# CH32M030G8R7_1V1.net
KiCad netlist of a schematic drawn in Altium Designer
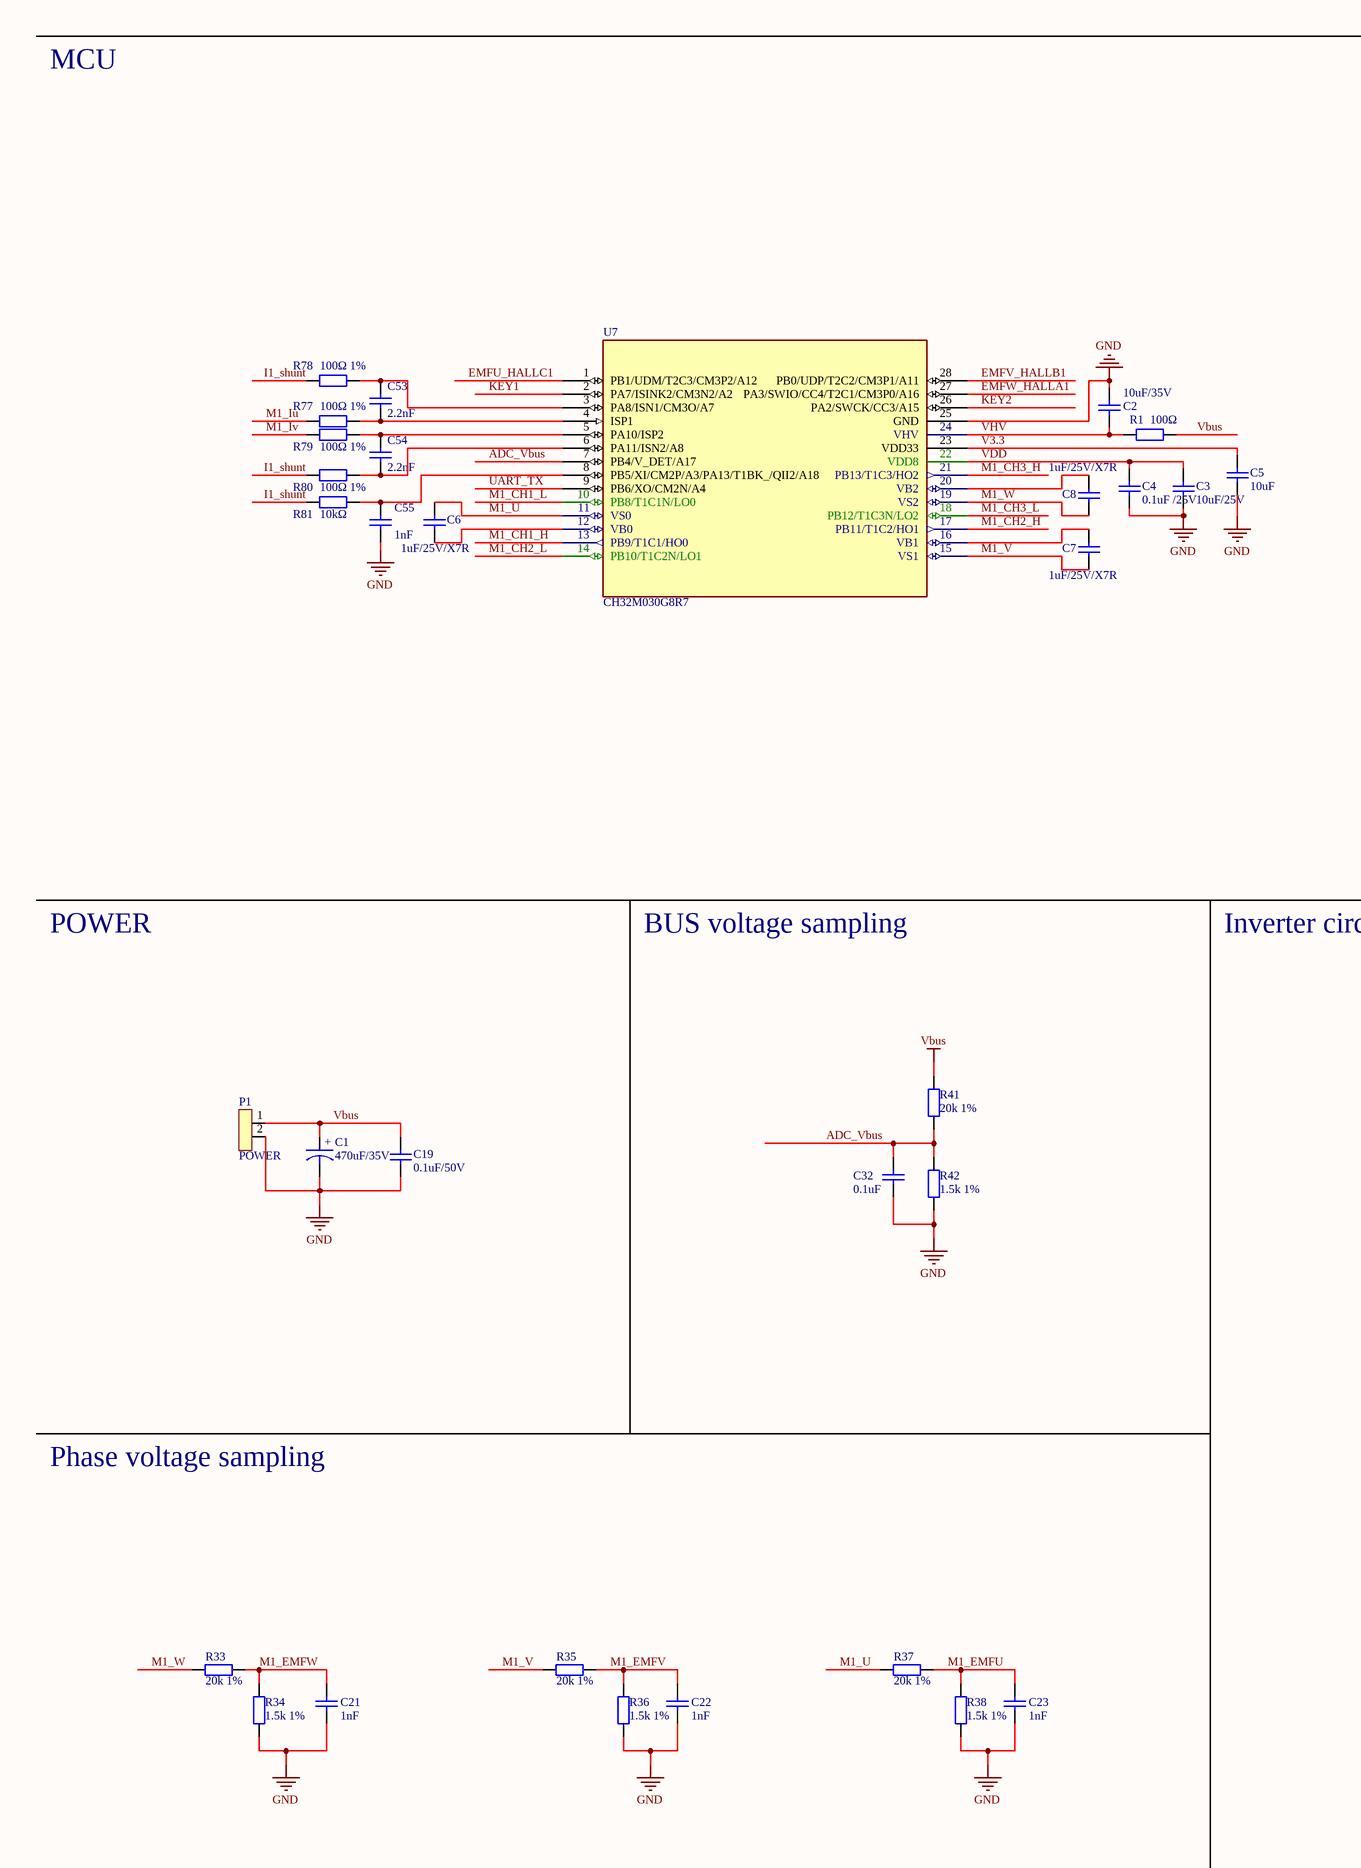
[diagram p0: CH32M030G8R7_1V1.SchDoc, left]
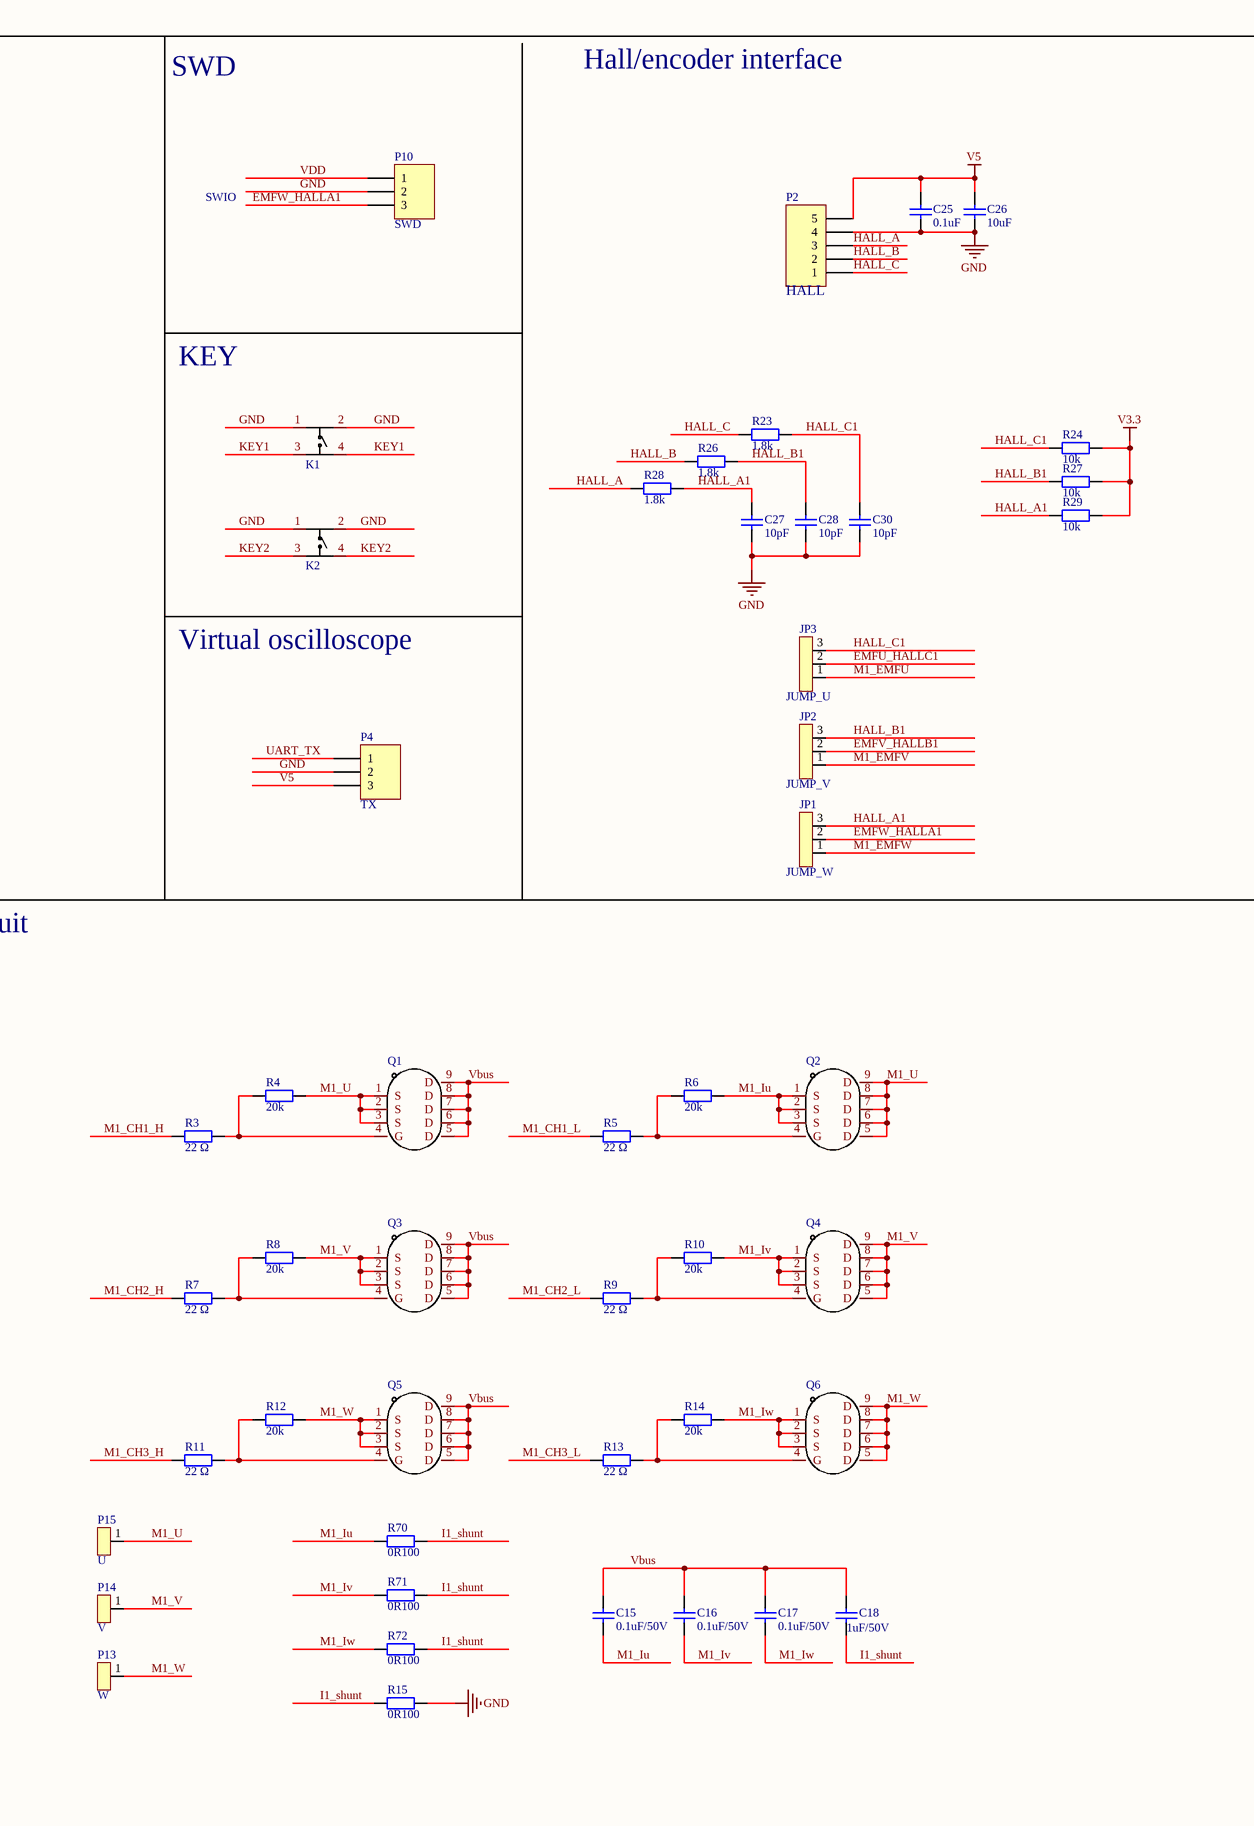
[diagram p1: CH32M030G8R7_1V1.SchDoc, right]

(export (version "E")
  (design (tool "Eeschema 10.0.6"))
  (components
    (comp (ref "C1")
      (value "470uF/35V")
      (footprint "M_C_RB_D10F5")
      (description "Capacitor")
      (libsource (lib "SMARTCORTEX M3-1700_1") (part "CAPACITOR POL_2"))
    )
    (comp (ref "C2")
      (value "10uF/35V")
      (footprint "M_C0805-")
      (description "Capacitor (Semiconductor SIM Model)")
      (fields (field (name "PUBLISHER") "Altium Limited"))
      (libsource (lib "Miscellaneous Devices") (part "Cap Semi"))
    )
    (comp (ref "C3")
      (value "10uF/25V")
      (footprint "M_C0805-")
      (description "Capacitor (Semiconductor SIM Model)")
      (fields (field (name "PUBLISHER") "Altium Limited"))
      (libsource (lib "Miscellaneous Devices") (part "Cap Semi"))
    )
    (comp (ref "C4")
      (value "0.1uF /25V")
      (footprint "M_C0402-")
      (description "Capacitor (Semiconductor SIM Model)")
      (fields (field (name "PUBLISHER") "Altium Limited"))
      (libsource (lib "Miscellaneous Devices") (part "Cap Semi"))
    )
    (comp (ref "C5")
      (value "10uF")
      (footprint "M_C0603")
      (description "Capacitor (Semiconductor SIM Model)")
      (fields (field (name "PUBLISHER") "Altium Limited"))
      (libsource (lib "Miscellaneous Devices") (part "Cap Semi"))
    )
    (comp (ref "C6")
      (value "1uF/25V/X7R")
      (footprint "M_C0805")
      (description "Capacitor (Semiconductor SIM Model)")
      (fields (field (name "PUBLISHER") "Altium Limited"))
      (libsource (lib "Miscellaneous Devices") (part "Cap Semi"))
    )
    (comp (ref "C7")
      (value "1uF/25V/X7R")
      (footprint "M_C0805")
      (description "Capacitor (Semiconductor SIM Model)")
      (fields (field (name "PUBLISHER") "Altium Limited"))
      (libsource (lib "Miscellaneous Devices") (part "Cap Semi"))
    )
    (comp (ref "C8")
      (value "1uF/25V/X7R")
      (footprint "M_C0805")
      (description "Capacitor (Semiconductor SIM Model)")
      (fields (field (name "PUBLISHER") "Altium Limited"))
      (libsource (lib "Miscellaneous Devices") (part "Cap Semi"))
    )
    (comp (ref "C15")
      (value "0.1uF/50V")
      (footprint "M_C0402-")
      (description "Capacitor (Semiconductor SIM Model)")
      (fields (field (name "PUBLISHER") "Altium Limited"))
      (libsource (lib "Miscellaneous Devices") (part "Cap Semi"))
    )
    (comp (ref "C16")
      (value "0.1uF/50V")
      (footprint "M_C0402-")
      (description "Capacitor (Semiconductor SIM Model)")
      (fields (field (name "PUBLISHER") "Altium Limited"))
      (libsource (lib "Miscellaneous Devices") (part "Cap Semi"))
    )
    (comp (ref "C17")
      (value "0.1uF/50V")
      (footprint "M_C0402-")
      (description "Capacitor (Semiconductor SIM Model)")
      (fields (field (name "PUBLISHER") "Altium Limited"))
      (libsource (lib "Miscellaneous Devices") (part "Cap Semi"))
    )
    (comp (ref "C18")
      (value "1uF/50V")
      (footprint "M_C0805-")
      (description "Capacitor (Semiconductor SIM Model)")
      (fields (field (name "PUBLISHER") "Altium Limited"))
      (libsource (lib "Miscellaneous Devices") (part "Cap Semi"))
    )
    (comp (ref "C19")
      (value "0.1uF/50V")
      (footprint "M_C0402-")
      (description "Capacitor (Semiconductor SIM Model)")
      (fields (field (name "PUBLISHER") "Altium Limited"))
      (libsource (lib "Miscellaneous Devices") (part "Cap Semi"))
    )
    (comp (ref "C21")
      (value "1nF")
      (footprint "M_C0402-")
      (description "Capacitor (Semiconductor SIM Model)")
      (fields (field (name "PUBLISHER") "Altium Limited"))
      (libsource (lib "Miscellaneous Devices") (part "Cap Semi"))
    )
    (comp (ref "C22")
      (value "1nF")
      (footprint "M_C0402-")
      (description "Capacitor (Semiconductor SIM Model)")
      (fields (field (name "PUBLISHER") "Altium Limited"))
      (libsource (lib "Miscellaneous Devices") (part "Cap Semi"))
    )
    (comp (ref "C23")
      (value "1nF")
      (footprint "M_C0402-")
      (description "Capacitor (Semiconductor SIM Model)")
      (fields (field (name "PUBLISHER") "Altium Limited"))
      (libsource (lib "Miscellaneous Devices") (part "Cap Semi"))
    )
    (comp (ref "C25")
      (value "0.1uF")
      (footprint "0603")
      (description "Capacitor (Semiconductor SIM Model)")
      (fields (field (name "PUBLISHER") "Altium Limited"))
      (libsource (lib "Miscellaneous Devices") (part "Cap Semi"))
    )
    (comp (ref "C26")
      (value "10uF")
      (footprint "0603")
      (description "Capacitor (Semiconductor SIM Model)")
      (fields (field (name "PUBLISHER") "Altium Limited"))
      (libsource (lib "Miscellaneous Devices") (part "Cap Semi"))
    )
    (comp (ref "C27")
      (value "10pF")
      (footprint "0603")
      (description "Capacitor (Semiconductor SIM Model)")
      (fields (field (name "PUBLISHER") "Altium Limited"))
      (libsource (lib "Miscellaneous Devices") (part "Cap Semi"))
    )
    (comp (ref "C28")
      (value "10pF")
      (footprint "0603")
      (description "Capacitor (Semiconductor SIM Model)")
      (fields (field (name "PUBLISHER") "Altium Limited"))
      (libsource (lib "Miscellaneous Devices") (part "Cap Semi"))
    )
    (comp (ref "C30")
      (value "10pF")
      (footprint "0603")
      (description "Capacitor (Semiconductor SIM Model)")
      (fields (field (name "PUBLISHER") "Altium Limited"))
      (libsource (lib "Miscellaneous Devices") (part "Cap Semi"))
    )
    (comp (ref "C32")
      (value "0.1uF")
      (footprint "M_C0402-")
      (description "Capacitor (Semiconductor SIM Model)")
      (fields (field (name "PUBLISHER") "Altium Limited"))
      (libsource (lib "Miscellaneous Devices") (part "Cap Semi"))
    )
    (comp (ref "C53")
      (value "2.2nF")
      (footprint "M_C0402-")
      (description "Capacitor (Semiconductor SIM Model)")
      (fields (field (name "PUBLISHER") "Altium Limited"))
      (libsource (lib "Miscellaneous Devices") (part "Cap Semi"))
    )
    (comp (ref "C54")
      (value "2.2nF")
      (footprint "M_C0402-")
      (description "Capacitor (Semiconductor SIM Model)")
      (fields (field (name "PUBLISHER") "Altium Limited"))
      (libsource (lib "Miscellaneous Devices") (part "Cap Semi"))
    )
    (comp (ref "C55")
      (value "1nF")
      (footprint "M_C0402-")
      (description "Capacitor (Semiconductor SIM Model)")
      (fields (field (name "PUBLISHER") "Altium Limited"))
      (libsource (lib "Miscellaneous Devices") (part "Cap Semi"))
    )
    (comp (ref "JP1")
      (value "JUMP_W")
      (footprint "HDR2.54-LI-3P")
      (libsource (lib "SUNWIN_SCH") (part "3PIN"))
    )
    (comp (ref "JP2")
      (value "JUMP_V")
      (footprint "HDR2.54-LI-3P")
      (libsource (lib "SUNWIN_SCH") (part "3PIN"))
    )
    (comp (ref "JP3")
      (value "JUMP_U")
      (footprint "HDR2.54-LI-3P")
      (libsource (lib "SUNWIN_SCH") (part "3PIN"))
    )
    (comp (ref "K1")
      (value "KH-6X6X8H-STM")
      (footprint "KEY2-SMD")
      (libsource (lib "altium-import") (part "root_0_KH-6X6X8H-STM_"))
    )
    (comp (ref "K2")
      (value "KH-6X6X8H-STM")
      (footprint "KEY2-SMD")
      (libsource (lib "altium-import") (part "root_0_KH-6X6X8H-STM_"))
    )
    (comp (ref "P1")
      (value "POWER")
      (footprint "WJ15EDGRC3.81-2")
      (libsource (lib "SUNWIN_SCH") (part "2PIN"))
    )
    (comp (ref "P2")
      (value "Header 5")
      (footprint "2510-5")
      (description "Header, 5-Pin")
      (fields (field (name "PUBLISHER") "Altium Limited"))
      (libsource (lib "Miscellaneous Connectors") (part "Header 5"))
    )
    (comp (ref "P4")
      (value "TX")
      (footprint "HDR2.54-LI-3P")
      (description "Header, 3-Pin")
      (libsource (lib "wch_sch_others") (part "HEADER 3"))
    )
    (comp (ref "P10")
      (value "SWD")
      (footprint "HDR2.54-LI-3P")
      (description "Header, 3-Pin")
      (libsource (lib "wch_sch_others") (part "HEADER 3"))
    )
    (comp (ref "P13")
      (value "W")
      (footprint "M_PAD-2.4/3.7")
      (description "CONNECTOR")
      (libsource (lib "SUNWIN_SCH") (part "1PIN"))
    )
    (comp (ref "P14")
      (value "V")
      (footprint "M_PAD-2.4/3.7")
      (description "CONNECTOR")
      (libsource (lib "SUNWIN_SCH") (part "1PIN"))
    )
    (comp (ref "P15")
      (value "U")
      (footprint "M_PAD-2.4/3.7")
      (description "CONNECTOR")
      (libsource (lib "SUNWIN_SCH") (part "1PIN"))
    )
    (comp (ref "Q1")
      (value "NP160S04PD6")
      (footprint "M_PDFN-8_L5.8-W4.9")
      (fields (field (name "MANUFACTURER PART") "NP100N03D6"))
      (libsource (lib "altium-import") (part "root_0_NP100N03D6_"))
    )
    (comp (ref "Q2")
      (value "NP160S04PD6")
      (footprint "M_PDFN-8_L5.8-W4.9")
      (fields (field (name "MANUFACTURER PART") "NP100N03D6"))
      (libsource (lib "altium-import") (part "root_0_NP100N03D6_"))
    )
    (comp (ref "Q3")
      (value "NP160S04PD6")
      (footprint "M_PDFN-8_L5.8-W4.9")
      (fields (field (name "MANUFACTURER PART") "NP100N03D6"))
      (libsource (lib "altium-import") (part "root_0_NP100N03D6_"))
    )
    (comp (ref "Q4")
      (value "NP160S04PD6")
      (footprint "M_PDFN-8_L5.8-W4.9")
      (fields (field (name "MANUFACTURER PART") "NP100N03D6"))
      (libsource (lib "altium-import") (part "root_0_NP100N03D6_"))
    )
    (comp (ref "Q5")
      (value "NP160S04PD6")
      (footprint "M_PDFN-8_L5.8-W4.9")
      (fields (field (name "MANUFACTURER PART") "NP100N03D6"))
      (libsource (lib "altium-import") (part "root_0_NP100N03D6_"))
    )
    (comp (ref "Q6")
      (value "NP160S04PD6")
      (footprint "M_PDFN-8_L5.8-W4.9")
      (fields (field (name "MANUFACTURER PART") "NP100N03D6"))
      (libsource (lib "altium-import") (part "root_0_NP100N03D6_"))
    )
    (comp (ref "R1")
      (value "100Ω")
      (footprint "M_R1206-")
      (description "Resistor")
      (fields (field (name "PUBLISHER") "Altium Limited"))
      (libsource (lib "") (part "Res2_1"))
    )
    (comp (ref "R3")
      (value "22 Ω")
      (footprint "M_R0402-")
      (description "Resistor")
      (fields (field (name "PUBLISHER") "Altium Limited"))
      (libsource (lib "") (part "Res2_1"))
    )
    (comp (ref "R4")
      (value "20k")
      (footprint "M_R0402-")
      (description "Resistor")
      (fields (field (name "PUBLISHER") "Altium Limited"))
      (libsource (lib "") (part "Res2_1"))
    )
    (comp (ref "R5")
      (value "22 Ω")
      (footprint "M_R0402-")
      (description "Resistor")
      (fields (field (name "PUBLISHER") "Altium Limited"))
      (libsource (lib "") (part "Res2_1"))
    )
    (comp (ref "R6")
      (value "20k")
      (footprint "M_R0402-")
      (description "Resistor")
      (fields (field (name "PUBLISHER") "Altium Limited"))
      (libsource (lib "") (part "Res2_1"))
    )
    (comp (ref "R7")
      (value "22 Ω")
      (footprint "M_R0402-")
      (description "Resistor")
      (fields (field (name "PUBLISHER") "Altium Limited"))
      (libsource (lib "") (part "Res2_1"))
    )
    (comp (ref "R8")
      (value "20k")
      (footprint "M_R0402-")
      (description "Resistor")
      (fields (field (name "PUBLISHER") "Altium Limited"))
      (libsource (lib "") (part "Res2_1"))
    )
    (comp (ref "R9")
      (value "22 Ω")
      (footprint "M_R0402-")
      (description "Resistor")
      (fields (field (name "PUBLISHER") "Altium Limited"))
      (libsource (lib "") (part "Res2_1"))
    )
    (comp (ref "R10")
      (value "20k")
      (footprint "M_R0402-")
      (description "Resistor")
      (fields (field (name "PUBLISHER") "Altium Limited"))
      (libsource (lib "") (part "Res2_1"))
    )
    (comp (ref "R11")
      (value "22 Ω")
      (footprint "M_R0402-")
      (description "Resistor")
      (fields (field (name "PUBLISHER") "Altium Limited"))
      (libsource (lib "") (part "Res2_1"))
    )
    (comp (ref "R12")
      (value "20k")
      (footprint "M_R0402-")
      (description "Resistor")
      (fields (field (name "PUBLISHER") "Altium Limited"))
      (libsource (lib "") (part "Res2_1"))
    )
    (comp (ref "R13")
      (value "22 Ω")
      (footprint "M_R0402-")
      (description "Resistor")
      (fields (field (name "PUBLISHER") "Altium Limited"))
      (libsource (lib "") (part "Res2_1"))
    )
    (comp (ref "R14")
      (value "20k")
      (footprint "M_R0402-")
      (description "Resistor")
      (fields (field (name "PUBLISHER") "Altium Limited"))
      (libsource (lib "") (part "Res2_1"))
    )
    (comp (ref "R15")
      (value "0R100")
      (footprint "M_R2512")
      (description "Resistor")
      (fields (field (name "PUBLISHER") "Altium Limited"))
      (libsource (lib "") (part "Res2_1"))
    )
    (comp (ref "R23")
      (value "1.8k")
      (footprint "0603")
      (description "Resistor")
      (fields (field (name "PUBLISHER") "Altium Limited"))
      (libsource (lib "Miscellaneous Devices") (part "Res2"))
    )
    (comp (ref "R24")
      (value "10k")
      (footprint "M_R0402-")
      (description "Resistor")
      (fields (field (name "PUBLISHER") "Altium Limited"))
      (libsource (lib "") (part "Res2_1"))
    )
    (comp (ref "R26")
      (value "1.8k")
      (footprint "0603")
      (description "Resistor")
      (fields (field (name "PUBLISHER") "Altium Limited"))
      (libsource (lib "Miscellaneous Devices") (part "Res2"))
    )
    (comp (ref "R27")
      (value "10k")
      (footprint "M_R0402-")
      (description "Resistor")
      (fields (field (name "PUBLISHER") "Altium Limited"))
      (libsource (lib "") (part "Res2_1"))
    )
    (comp (ref "R28")
      (value "1.8k")
      (footprint "0603")
      (description "Resistor")
      (fields (field (name "PUBLISHER") "Altium Limited"))
      (libsource (lib "Miscellaneous Devices") (part "Res2"))
    )
    (comp (ref "R29")
      (value "10k")
      (footprint "M_R0402-")
      (description "Resistor")
      (fields (field (name "PUBLISHER") "Altium Limited"))
      (libsource (lib "") (part "Res2_1"))
    )
    (comp (ref "R33")
      (value "20k 1%")
      (footprint "M_R0603")
      (description "Resistor")
      (fields (field (name "PUBLISHER") "Altium Limited"))
      (libsource (lib "") (part "Res2_1"))
    )
    (comp (ref "R34")
      (value "1.5k 1%")
      (footprint "M_R0402-")
      (description "Resistor")
      (fields (field (name "PUBLISHER") "Altium Limited"))
      (libsource (lib "") (part "Res2_2"))
    )
    (comp (ref "R35")
      (value "20k 1%")
      (footprint "M_R0603")
      (description "Resistor")
      (fields (field (name "PUBLISHER") "Altium Limited"))
      (libsource (lib "") (part "Res2_1"))
    )
    (comp (ref "R36")
      (value "1.5k 1%")
      (footprint "M_R0402-")
      (description "Resistor")
      (fields (field (name "PUBLISHER") "Altium Limited"))
      (libsource (lib "") (part "Res2_2"))
    )
    (comp (ref "R37")
      (value "20k 1%")
      (footprint "M_R0603")
      (description "Resistor")
      (fields (field (name "PUBLISHER") "Altium Limited"))
      (libsource (lib "") (part "Res2_1"))
    )
    (comp (ref "R38")
      (value "1.5k 1%")
      (footprint "M_R0402-")
      (description "Resistor")
      (fields (field (name "PUBLISHER") "Altium Limited"))
      (libsource (lib "") (part "Res2_2"))
    )
    (comp (ref "R41")
      (value "20k 1%")
      (footprint "M_R0603")
      (description "Resistor")
      (fields (field (name "PUBLISHER") "Altium Limited"))
      (libsource (lib "") (part "Res2_2"))
    )
    (comp (ref "R42")
      (value "1.5k 1%")
      (footprint "M_R0402-")
      (description "Resistor")
      (fields (field (name "PUBLISHER") "Altium Limited"))
      (libsource (lib "") (part "Res2_2"))
    )
    (comp (ref "R70")
      (value "0R100")
      (footprint "M_R2512")
      (description "Resistor")
      (fields (field (name "PUBLISHER") "Altium Limited"))
      (libsource (lib "") (part "Res2_1"))
    )
    (comp (ref "R71")
      (value "0R100")
      (footprint "M_R2512")
      (description "Resistor")
      (fields (field (name "PUBLISHER") "Altium Limited"))
      (libsource (lib "") (part "Res2_1"))
    )
    (comp (ref "R72")
      (value "0R100")
      (footprint "M_R2512")
      (description "Resistor")
      (fields (field (name "PUBLISHER") "Altium Limited"))
      (libsource (lib "") (part "Res2_1"))
    )
    (comp (ref "R77")
      (value "100Ω 1%")
      (footprint "M_R0402-")
      (description "Resistor")
      (fields (field (name "PUBLISHER") "Altium Limited"))
      (libsource (lib "Miscellaneous Devices") (part "Res2"))
    )
    (comp (ref "R78")
      (value "100Ω 1%")
      (footprint "M_R0402-")
      (description "Resistor")
      (fields (field (name "PUBLISHER") "Altium Limited"))
      (libsource (lib "Miscellaneous Devices") (part "Res2"))
    )
    (comp (ref "R79")
      (value "100Ω 1%")
      (footprint "M_R0402-")
      (description "Resistor")
      (fields (field (name "PUBLISHER") "Altium Limited"))
      (libsource (lib "Miscellaneous Devices") (part "Res2"))
    )
    (comp (ref "R80")
      (value "100Ω 1%")
      (footprint "M_R0402-")
      (description "Resistor")
      (fields (field (name "PUBLISHER") "Altium Limited"))
      (libsource (lib "Miscellaneous Devices") (part "Res2"))
    )
    (comp (ref "R81")
      (value "10kΩ")
      (footprint "M_R0402-")
      (description "Resistor")
      (fields (field (name "PUBLISHER") "Altium Limited"))
      (libsource (lib "Miscellaneous Devices") (part "Res2"))
    )
    (comp (ref "U7")
      (value "CH32M030G8R7")
      (footprint "QSOP28")
      (description "RISC-V MCU, 72MHz, USB, Type-C/PD, OPA, CMP, 28V gate driver")
      (libsource (lib "CHXXX") (part "CH32M030G8R7"))
    )
  )
  (nets
    (net (code "1") (name "/ADC_Vbus") (class "Default")
      (node (ref "C32") (pin "1") (pinfunction "1_1") (pintype "passive"))
      (node (ref "R41") (pin "1") (pinfunction "1_1") (pintype "passive"))
      (node (ref "R42") (pin "2") (pinfunction "2_2") (pintype "passive"))
      (node (ref "U7") (pin "7") (pinfunction "PB4/V_DET/A17_7") (pintype "bidirectional"))
    )
    (net (code "2") (name "/EMFU_HALLC1") (class "Default")
      (node (ref "JP3") (pin "2") (pintype "passive"))
      (node (ref "U7") (pin "1") (pinfunction "PB1/UDM/T2C3/CM3P2/A12_1") (pintype "bidirectional"))
    )
    (net (code "3") (name "/EMFV_HALLB1") (class "Default")
      (node (ref "JP2") (pin "2") (pintype "passive"))
      (node (ref "U7") (pin "28") (pinfunction "PB0/UDP/T2C2/CM3P1/A11_28") (pintype "bidirectional"))
    )
    (net (code "4") (name "/EMFW_HALLA1") (class "Default")
      (node (ref "JP1") (pin "2") (pintype "passive"))
      (node (ref "P10") (pin "3") (pinfunction "3_3") (pintype "passive"))
      (node (ref "U7") (pin "27") (pinfunction "PA3/SWIO/CC4/T2C1/CM3P0/A16_27") (pintype "bidirectional"))
    )
    (net (code "5") (name "/HALL_A") (class "Default")
      (node (ref "P2") (pin "3") (pinfunction "3_3") (pintype "passive"))
      (node (ref "R28") (pin "1") (pinfunction "1_1") (pintype "passive"))
    )
    (net (code "6") (name "/HALL_A1") (class "Default")
      (node (ref "C27") (pin "1") (pinfunction "1_1") (pintype "passive"))
      (node (ref "JP1") (pin "3") (pintype "passive"))
      (node (ref "R28") (pin "2") (pinfunction "2_2") (pintype "passive"))
      (node (ref "R29") (pin "2") (pinfunction "2_2") (pintype "passive"))
    )
    (net (code "7") (name "/HALL_B") (class "Default")
      (node (ref "P2") (pin "2") (pinfunction "2_2") (pintype "passive"))
      (node (ref "R26") (pin "1") (pinfunction "1_1") (pintype "passive"))
    )
    (net (code "8") (name "/HALL_B1") (class "Default")
      (node (ref "C28") (pin "1") (pinfunction "1_1") (pintype "passive"))
      (node (ref "JP2") (pin "3") (pintype "passive"))
      (node (ref "R26") (pin "2") (pinfunction "2_2") (pintype "passive"))
      (node (ref "R27") (pin "2") (pinfunction "2_2") (pintype "passive"))
    )
    (net (code "9") (name "/HALL_C") (class "Default")
      (node (ref "P2") (pin "1") (pinfunction "1_1") (pintype "passive"))
      (node (ref "R23") (pin "1") (pinfunction "1_1") (pintype "passive"))
    )
    (net (code "10") (name "/HALL_C1") (class "Default")
      (node (ref "C30") (pin "1") (pinfunction "1_1") (pintype "passive"))
      (node (ref "JP3") (pin "3") (pintype "passive"))
      (node (ref "R23") (pin "2") (pinfunction "2_2") (pintype "passive"))
      (node (ref "R24") (pin "2") (pinfunction "2_2") (pintype "passive"))
    )
    (net (code "11") (name "/I1_shunt") (class "Default")
      (node (ref "C18") (pin "2") (pinfunction "2_2") (pintype "passive"))
      (node (ref "R15") (pin "2") (pinfunction "2_2") (pintype "passive"))
      (node (ref "R70") (pin "1") (pinfunction "1_1") (pintype "passive"))
      (node (ref "R71") (pin "1") (pinfunction "1_1") (pintype "passive"))
      (node (ref "R72") (pin "1") (pinfunction "1_1") (pintype "passive"))
      (node (ref "R78") (pin "1") (pinfunction "1_1") (pintype "passive"))
      (node (ref "R80") (pin "1") (pinfunction "1_1") (pintype "passive"))
      (node (ref "R81") (pin "1") (pinfunction "1_1") (pintype "passive"))
    )
    (net (code "12") (name "/KEY1") (class "Default")
      (node (ref "K1") (pin "3") (pinfunction "C_3") (pintype "passive"))
      (node (ref "K1") (pin "4") (pinfunction "D_4") (pintype "passive"))
      (node (ref "U7") (pin "2") (pinfunction "PA7/ISINK2/CM3N2/A2_2") (pintype "bidirectional"))
    )
    (net (code "13") (name "/KEY2") (class "Default")
      (node (ref "K2") (pin "3") (pinfunction "C_3") (pintype "passive"))
      (node (ref "K2") (pin "4") (pinfunction "D_4") (pintype "passive"))
      (node (ref "U7") (pin "26") (pinfunction "PA2/SWCK/CC3/A15_26") (pintype "bidirectional"))
    )
    (net (code "14") (name "/M1_CH1_H") (class "Default")
      (node (ref "R3") (pin "2") (pinfunction "2_2") (pintype "passive"))
      (node (ref "U7") (pin "13") (pinfunction "PB9/T1C1/HO0_13") (pintype "output"))
    )
    (net (code "15") (name "/M1_CH1_L") (class "Default")
      (node (ref "R5") (pin "2") (pinfunction "2_2") (pintype "passive"))
      (node (ref "U7") (pin "10") (pinfunction "PB8/T1C1N/LO0_10") (pintype "bidirectional"))
    )
    (net (code "16") (name "/M1_CH2_H") (class "Default")
      (node (ref "R7") (pin "2") (pinfunction "2_2") (pintype "passive"))
      (node (ref "U7") (pin "17") (pinfunction "PB11/T1C2/HO1_17") (pintype "output"))
    )
    (net (code "17") (name "/M1_CH2_L") (class "Default")
      (node (ref "R9") (pin "2") (pinfunction "2_2") (pintype "passive"))
      (node (ref "U7") (pin "14") (pinfunction "PB10/T1C2N/LO1_14") (pintype "bidirectional"))
    )
    (net (code "18") (name "/M1_CH3_H") (class "Default")
      (node (ref "R11") (pin "2") (pinfunction "2_2") (pintype "passive"))
      (node (ref "U7") (pin "21") (pinfunction "PB13/T1C3/HO2_21") (pintype "output"))
    )
    (net (code "19") (name "/M1_CH3_L") (class "Default")
      (node (ref "R13") (pin "2") (pinfunction "2_2") (pintype "passive"))
      (node (ref "U7") (pin "18") (pinfunction "PB12/T1C3N/LO2_18") (pintype "bidirectional"))
    )
    (net (code "20") (name "/M1_EMFU") (class "Default")
      (node (ref "C23") (pin "1") (pinfunction "1_1") (pintype "passive"))
      (node (ref "JP3") (pin "1") (pintype "passive"))
      (node (ref "R37") (pin "1") (pinfunction "1_1") (pintype "passive"))
      (node (ref "R38") (pin "2") (pinfunction "2_2") (pintype "passive"))
    )
    (net (code "21") (name "/M1_EMFV") (class "Default")
      (node (ref "C22") (pin "1") (pinfunction "1_1") (pintype "passive"))
      (node (ref "JP2") (pin "1") (pintype "passive"))
      (node (ref "R35") (pin "1") (pinfunction "1_1") (pintype "passive"))
      (node (ref "R36") (pin "2") (pinfunction "2_2") (pintype "passive"))
    )
    (net (code "22") (name "/M1_EMFW") (class "Default")
      (node (ref "C21") (pin "1") (pinfunction "1_1") (pintype "passive"))
      (node (ref "JP1") (pin "1") (pintype "passive"))
      (node (ref "R33") (pin "1") (pinfunction "1_1") (pintype "passive"))
      (node (ref "R34") (pin "2") (pinfunction "2_2") (pintype "passive"))
    )
    (net (code "23") (name "/M1_Iu") (class "Default")
      (node (ref "C15") (pin "2") (pinfunction "2_2") (pintype "passive"))
      (node (ref "Q2") (pin "1") (pinfunction "S_1") (pintype "passive"))
      (node (ref "Q2") (pin "2") (pinfunction "S_2") (pintype "passive"))
      (node (ref "Q2") (pin "3") (pinfunction "S_3") (pintype "passive"))
      (node (ref "R6") (pin "1") (pinfunction "1_1") (pintype "passive"))
      (node (ref "R70") (pin "2") (pinfunction "2_2") (pintype "passive"))
      (node (ref "R77") (pin "1") (pinfunction "1_1") (pintype "passive"))
    )
    (net (code "24") (name "/M1_Iv") (class "Default")
      (node (ref "C16") (pin "2") (pinfunction "2_2") (pintype "passive"))
      (node (ref "Q4") (pin "1") (pinfunction "S_1") (pintype "passive"))
      (node (ref "Q4") (pin "2") (pinfunction "S_2") (pintype "passive"))
      (node (ref "Q4") (pin "3") (pinfunction "S_3") (pintype "passive"))
      (node (ref "R10") (pin "1") (pinfunction "1_1") (pintype "passive"))
      (node (ref "R71") (pin "2") (pinfunction "2_2") (pintype "passive"))
      (node (ref "R79") (pin "1") (pinfunction "1_1") (pintype "passive"))
    )
    (net (code "25") (name "/M1_Iw") (class "Default")
      (node (ref "C17") (pin "2") (pinfunction "2_2") (pintype "passive"))
      (node (ref "Q6") (pin "1") (pinfunction "S_1") (pintype "passive"))
      (node (ref "Q6") (pin "2") (pinfunction "S_2") (pintype "passive"))
      (node (ref "Q6") (pin "3") (pinfunction "S_3") (pintype "passive"))
      (node (ref "R14") (pin "1") (pinfunction "1_1") (pintype "passive"))
      (node (ref "R72") (pin "2") (pinfunction "2_2") (pintype "passive"))
    )
    (net (code "26") (name "/M1_U") (class "Default")
      (node (ref "C6") (pin "2") (pinfunction "2_2") (pintype "passive"))
      (node (ref "P15") (pin "1") (pintype "passive"))
      (node (ref "Q1") (pin "1") (pinfunction "S_1") (pintype "passive"))
      (node (ref "Q1") (pin "2") (pinfunction "S_2") (pintype "passive"))
      (node (ref "Q1") (pin "3") (pinfunction "S_3") (pintype "passive"))
      (node (ref "Q2") (pin "5") (pinfunction "D_5") (pintype "passive"))
      (node (ref "Q2") (pin "6") (pinfunction "D_6") (pintype "passive"))
      (node (ref "Q2") (pin "7") (pinfunction "D_7") (pintype "passive"))
      (node (ref "Q2") (pin "8") (pinfunction "D_8") (pintype "passive"))
      (node (ref "Q2") (pin "9") (pinfunction "D_9") (pintype "passive"))
      (node (ref "R37") (pin "2") (pinfunction "2_2") (pintype "passive"))
      (node (ref "R4") (pin "1") (pinfunction "1_1") (pintype "passive"))
      (node (ref "U7") (pin "11") (pinfunction "VS0_11") (pintype "bidirectional"))
    )
    (net (code "27") (name "/M1_V") (class "Default")
      (node (ref "C7") (pin "2") (pinfunction "2_2") (pintype "passive"))
      (node (ref "P14") (pin "1") (pintype "passive"))
      (node (ref "Q3") (pin "1") (pinfunction "S_1") (pintype "passive"))
      (node (ref "Q3") (pin "2") (pinfunction "S_2") (pintype "passive"))
      (node (ref "Q3") (pin "3") (pinfunction "S_3") (pintype "passive"))
      (node (ref "Q4") (pin "5") (pinfunction "D_5") (pintype "passive"))
      (node (ref "Q4") (pin "6") (pinfunction "D_6") (pintype "passive"))
      (node (ref "Q4") (pin "7") (pinfunction "D_7") (pintype "passive"))
      (node (ref "Q4") (pin "8") (pinfunction "D_8") (pintype "passive"))
      (node (ref "Q4") (pin "9") (pinfunction "D_9") (pintype "passive"))
      (node (ref "R35") (pin "2") (pinfunction "2_2") (pintype "passive"))
      (node (ref "R8") (pin "1") (pinfunction "1_1") (pintype "passive"))
      (node (ref "U7") (pin "15") (pinfunction "VS1_15") (pintype "bidirectional"))
    )
    (net (code "28") (name "/M1_W") (class "Default")
      (node (ref "C8") (pin "2") (pinfunction "2_2") (pintype "passive"))
      (node (ref "P13") (pin "1") (pintype "passive"))
      (node (ref "Q5") (pin "1") (pinfunction "S_1") (pintype "passive"))
      (node (ref "Q5") (pin "2") (pinfunction "S_2") (pintype "passive"))
      (node (ref "Q5") (pin "3") (pinfunction "S_3") (pintype "passive"))
      (node (ref "Q6") (pin "5") (pinfunction "D_5") (pintype "passive"))
      (node (ref "Q6") (pin "6") (pinfunction "D_6") (pintype "passive"))
      (node (ref "Q6") (pin "7") (pinfunction "D_7") (pintype "passive"))
      (node (ref "Q6") (pin "8") (pinfunction "D_8") (pintype "passive"))
      (node (ref "Q6") (pin "9") (pinfunction "D_9") (pintype "passive"))
      (node (ref "R12") (pin "1") (pinfunction "1_1") (pintype "passive"))
      (node (ref "R33") (pin "2") (pinfunction "2_2") (pintype "passive"))
      (node (ref "U7") (pin "19") (pinfunction "VS2_19") (pintype "bidirectional"))
    )
    (net (code "29") (name "/UART_TX") (class "Default")
      (node (ref "P4") (pin "1") (pinfunction "1_1") (pintype "passive"))
      (node (ref "U7") (pin "9") (pinfunction "PB6/XO/CM2N/A4_9") (pintype "bidirectional"))
    )
    (net (code "30") (name "/VDD") (class "Default")
      (node (ref "C3") (pin "2") (pinfunction "2_2") (pintype "passive"))
      (node (ref "C4") (pin "1") (pinfunction "1_1") (pintype "passive"))
      (node (ref "P10") (pin "1") (pinfunction "1_1") (pintype "passive"))
      (node (ref "U7") (pin "22") (pinfunction "VDD8_22") (pintype "power_in"))
    )
    (net (code "31") (name "/VHV") (class "Default")
      (node (ref "C2") (pin "2") (pinfunction "2_2") (pintype "passive"))
      (node (ref "R1") (pin "2") (pinfunction "2_2") (pintype "passive"))
      (node (ref "U7") (pin "24") (pinfunction "VHV_24") (pintype "power_in"))
    )
    (net (code "32") (name "GND") (class "Default")
      (node (ref "C1") (pin "2") (pinfunction "2_2") (pintype "passive"))
      (node (ref "C19") (pin "2") (pinfunction "2_2") (pintype "passive"))
      (node (ref "C2") (pin "1") (pinfunction "1_1") (pintype "passive"))
      (node (ref "C21") (pin "2") (pinfunction "2_2") (pintype "passive"))
      (node (ref "C22") (pin "2") (pinfunction "2_2") (pintype "passive"))
      (node (ref "C23") (pin "2") (pinfunction "2_2") (pintype "passive"))
      (node (ref "C25") (pin "2") (pinfunction "2_2") (pintype "passive"))
      (node (ref "C26") (pin "2") (pinfunction "2_2") (pintype "passive"))
      (node (ref "C27") (pin "2") (pinfunction "2_2") (pintype "passive"))
      (node (ref "C28") (pin "2") (pinfunction "2_2") (pintype "passive"))
      (node (ref "C3") (pin "1") (pinfunction "1_1") (pintype "passive"))
      (node (ref "C30") (pin "2") (pinfunction "2_2") (pintype "passive"))
      (node (ref "C32") (pin "2") (pinfunction "2_2") (pintype "passive"))
      (node (ref "C4") (pin "2") (pinfunction "2_2") (pintype "passive"))
      (node (ref "C5") (pin "1") (pinfunction "1_1") (pintype "passive"))
      (node (ref "C55") (pin "2") (pinfunction "2_2") (pintype "passive"))
      (node (ref "K1") (pin "1") (pinfunction "A_1") (pintype "passive"))
      (node (ref "K1") (pin "2") (pinfunction "B_2") (pintype "passive"))
      (node (ref "K2") (pin "1") (pinfunction "A_1") (pintype "passive"))
      (node (ref "K2") (pin "2") (pinfunction "B_2") (pintype "passive"))
      (node (ref "P1") (pin "2") (pintype "passive"))
      (node (ref "P10") (pin "2") (pinfunction "2_2") (pintype "passive"))
      (node (ref "P2") (pin "4") (pinfunction "4_4") (pintype "passive"))
      (node (ref "P4") (pin "2") (pinfunction "2_2") (pintype "passive"))
      (node (ref "R15") (pin "1") (pinfunction "1_1") (pintype "passive"))
      (node (ref "R34") (pin "1") (pinfunction "1_1") (pintype "passive"))
      (node (ref "R36") (pin "1") (pinfunction "1_1") (pintype "passive"))
      (node (ref "R38") (pin "1") (pinfunction "1_1") (pintype "passive"))
      (node (ref "R42") (pin "1") (pinfunction "1_1") (pintype "passive"))
      (node (ref "U7") (pin "25") (pinfunction "GND_25") (pintype "power_in"))
    )
    (net (code "33") (name "Net-(Q1-G)") (class "Default")
      (node (ref "Q1") (pin "4") (pinfunction "G_4") (pintype "passive"))
      (node (ref "R3") (pin "1") (pinfunction "1_1") (pintype "passive"))
      (node (ref "R4") (pin "2") (pinfunction "2_2") (pintype "passive"))
    )
    (net (code "34") (name "Net-(Q2-G)") (class "Default")
      (node (ref "Q2") (pin "4") (pinfunction "G_4") (pintype "passive"))
      (node (ref "R5") (pin "1") (pinfunction "1_1") (pintype "passive"))
      (node (ref "R6") (pin "2") (pinfunction "2_2") (pintype "passive"))
    )
    (net (code "35") (name "Net-(Q3-G)") (class "Default")
      (node (ref "Q3") (pin "4") (pinfunction "G_4") (pintype "passive"))
      (node (ref "R7") (pin "1") (pinfunction "1_1") (pintype "passive"))
      (node (ref "R8") (pin "2") (pinfunction "2_2") (pintype "passive"))
    )
    (net (code "36") (name "Net-(Q4-G)") (class "Default")
      (node (ref "Q4") (pin "4") (pinfunction "G_4") (pintype "passive"))
      (node (ref "R10") (pin "2") (pinfunction "2_2") (pintype "passive"))
      (node (ref "R9") (pin "1") (pinfunction "1_1") (pintype "passive"))
    )
    (net (code "37") (name "Net-(Q5-G)") (class "Default")
      (node (ref "Q5") (pin "4") (pinfunction "G_4") (pintype "passive"))
      (node (ref "R11") (pin "1") (pinfunction "1_1") (pintype "passive"))
      (node (ref "R12") (pin "2") (pinfunction "2_2") (pintype "passive"))
    )
    (net (code "38") (name "Net-(Q6-G)") (class "Default")
      (node (ref "Q6") (pin "4") (pinfunction "G_4") (pintype "passive"))
      (node (ref "R13") (pin "1") (pinfunction "1_1") (pintype "passive"))
      (node (ref "R14") (pin "2") (pinfunction "2_2") (pintype "passive"))
    )
    (net (code "39") (name "Net-(U7-ISP1)") (class "Default")
      (node (ref "C53") (pin "2") (pinfunction "2_2") (pintype "passive"))
      (node (ref "R77") (pin "2") (pinfunction "2_2") (pintype "passive"))
      (node (ref "U7") (pin "4") (pinfunction "ISP1_4") (pintype "input"))
    )
    (net (code "40") (name "Net-(U7-PA8{slash}ISN1{slash}CM3O{slash}A7)") (class "Default")
      (node (ref "C53") (pin "1") (pinfunction "1_1") (pintype "passive"))
      (node (ref "R78") (pin "2") (pinfunction "2_2") (pintype "passive"))
      (node (ref "U7") (pin "3") (pinfunction "PA8/ISN1/CM3O/A7_3") (pintype "bidirectional"))
    )
    (net (code "41") (name "Net-(U7-PA10{slash}ISP2)") (class "Default")
      (node (ref "C54") (pin "1") (pinfunction "1_1") (pintype "passive"))
      (node (ref "R79") (pin "2") (pinfunction "2_2") (pintype "passive"))
      (node (ref "U7") (pin "5") (pinfunction "PA10/ISP2_5") (pintype "bidirectional"))
    )
    (net (code "42") (name "Net-(U7-PA11{slash}ISN2{slash}A8)") (class "Default")
      (node (ref "C54") (pin "2") (pinfunction "2_2") (pintype "passive"))
      (node (ref "R80") (pin "2") (pinfunction "2_2") (pintype "passive"))
      (node (ref "U7") (pin "6") (pinfunction "PA11/ISN2/A8_6") (pintype "bidirectional"))
    )
    (net (code "43") (name "Net-(U7-PB5{slash}XI{slash}CM2P{slash}A3{slash}PA13{slash}T1BK_{slash}QII2{slash}A18)") (class "Default")
      (node (ref "C55") (pin "1") (pinfunction "1_1") (pintype "passive"))
      (node (ref "R81") (pin "2") (pinfunction "2_2") (pintype "passive"))
      (node (ref "U7") (pin "8") (pinfunction "PB5/XI/CM2P/A3/PA13/T1BK_/QII2/A18_8") (pintype "bidirectional"))
    )
    (net (code "44") (name "Net-(U7-VB0)") (class "Default")
      (node (ref "C6") (pin "1") (pinfunction "1_1") (pintype "passive"))
      (node (ref "U7") (pin "12") (pinfunction "VB0_12") (pintype "bidirectional"))
    )
    (net (code "45") (name "Net-(U7-VB1)") (class "Default")
      (node (ref "C7") (pin "1") (pinfunction "1_1") (pintype "passive"))
      (node (ref "U7") (pin "16") (pinfunction "VB1_16") (pintype "bidirectional"))
    )
    (net (code "46") (name "Net-(U7-VB2)") (class "Default")
      (node (ref "C8") (pin "1") (pinfunction "1_1") (pintype "passive"))
      (node (ref "U7") (pin "20") (pinfunction "VB2_20") (pintype "bidirectional"))
    )
    (net (code "47") (name "V3.3") (class "Default")
      (node (ref "C5") (pin "2") (pinfunction "2_2") (pintype "passive"))
      (node (ref "R24") (pin "1") (pinfunction "1_1") (pintype "passive"))
      (node (ref "R27") (pin "1") (pinfunction "1_1") (pintype "passive"))
      (node (ref "R29") (pin "1") (pinfunction "1_1") (pintype "passive"))
      (node (ref "U7") (pin "23") (pinfunction "VDD33_23") (pintype "power_in"))
    )
    (net (code "48") (name "V5") (class "Default")
      (node (ref "C25") (pin "1") (pinfunction "1_1") (pintype "passive"))
      (node (ref "C26") (pin "1") (pinfunction "1_1") (pintype "passive"))
      (node (ref "P2") (pin "5") (pinfunction "5_5") (pintype "passive"))
      (node (ref "P4") (pin "3") (pinfunction "3_3") (pintype "passive"))
    )
    (net (code "49") (name "Vbus") (class "Default")
      (node (ref "C1") (pin "1") (pinfunction "1_1") (pintype "passive"))
      (node (ref "C15") (pin "1") (pinfunction "1_1") (pintype "passive"))
      (node (ref "C16") (pin "1") (pinfunction "1_1") (pintype "passive"))
      (node (ref "C17") (pin "1") (pinfunction "1_1") (pintype "passive"))
      (node (ref "C18") (pin "1") (pinfunction "1_1") (pintype "passive"))
      (node (ref "C19") (pin "1") (pinfunction "1_1") (pintype "passive"))
      (node (ref "P1") (pin "1") (pintype "passive"))
      (node (ref "Q1") (pin "5") (pinfunction "D_5") (pintype "passive"))
      (node (ref "Q1") (pin "6") (pinfunction "D_6") (pintype "passive"))
      (node (ref "Q1") (pin "7") (pinfunction "D_7") (pintype "passive"))
      (node (ref "Q1") (pin "8") (pinfunction "D_8") (pintype "passive"))
      (node (ref "Q1") (pin "9") (pinfunction "D_9") (pintype "passive"))
      (node (ref "Q3") (pin "5") (pinfunction "D_5") (pintype "passive"))
      (node (ref "Q3") (pin "6") (pinfunction "D_6") (pintype "passive"))
      (node (ref "Q3") (pin "7") (pinfunction "D_7") (pintype "passive"))
      (node (ref "Q3") (pin "8") (pinfunction "D_8") (pintype "passive"))
      (node (ref "Q3") (pin "9") (pinfunction "D_9") (pintype "passive"))
      (node (ref "Q5") (pin "5") (pinfunction "D_5") (pintype "passive"))
      (node (ref "Q5") (pin "6") (pinfunction "D_6") (pintype "passive"))
      (node (ref "Q5") (pin "7") (pinfunction "D_7") (pintype "passive"))
      (node (ref "Q5") (pin "8") (pinfunction "D_8") (pintype "passive"))
      (node (ref "Q5") (pin "9") (pinfunction "D_9") (pintype "passive"))
      (node (ref "R1") (pin "1") (pinfunction "1_1") (pintype "passive"))
      (node (ref "R41") (pin "2") (pinfunction "2_2") (pintype "passive"))
    )
  )
)
